# SensorBreakout.net
KiCad netlist of a schematic drawn in Altium Designer
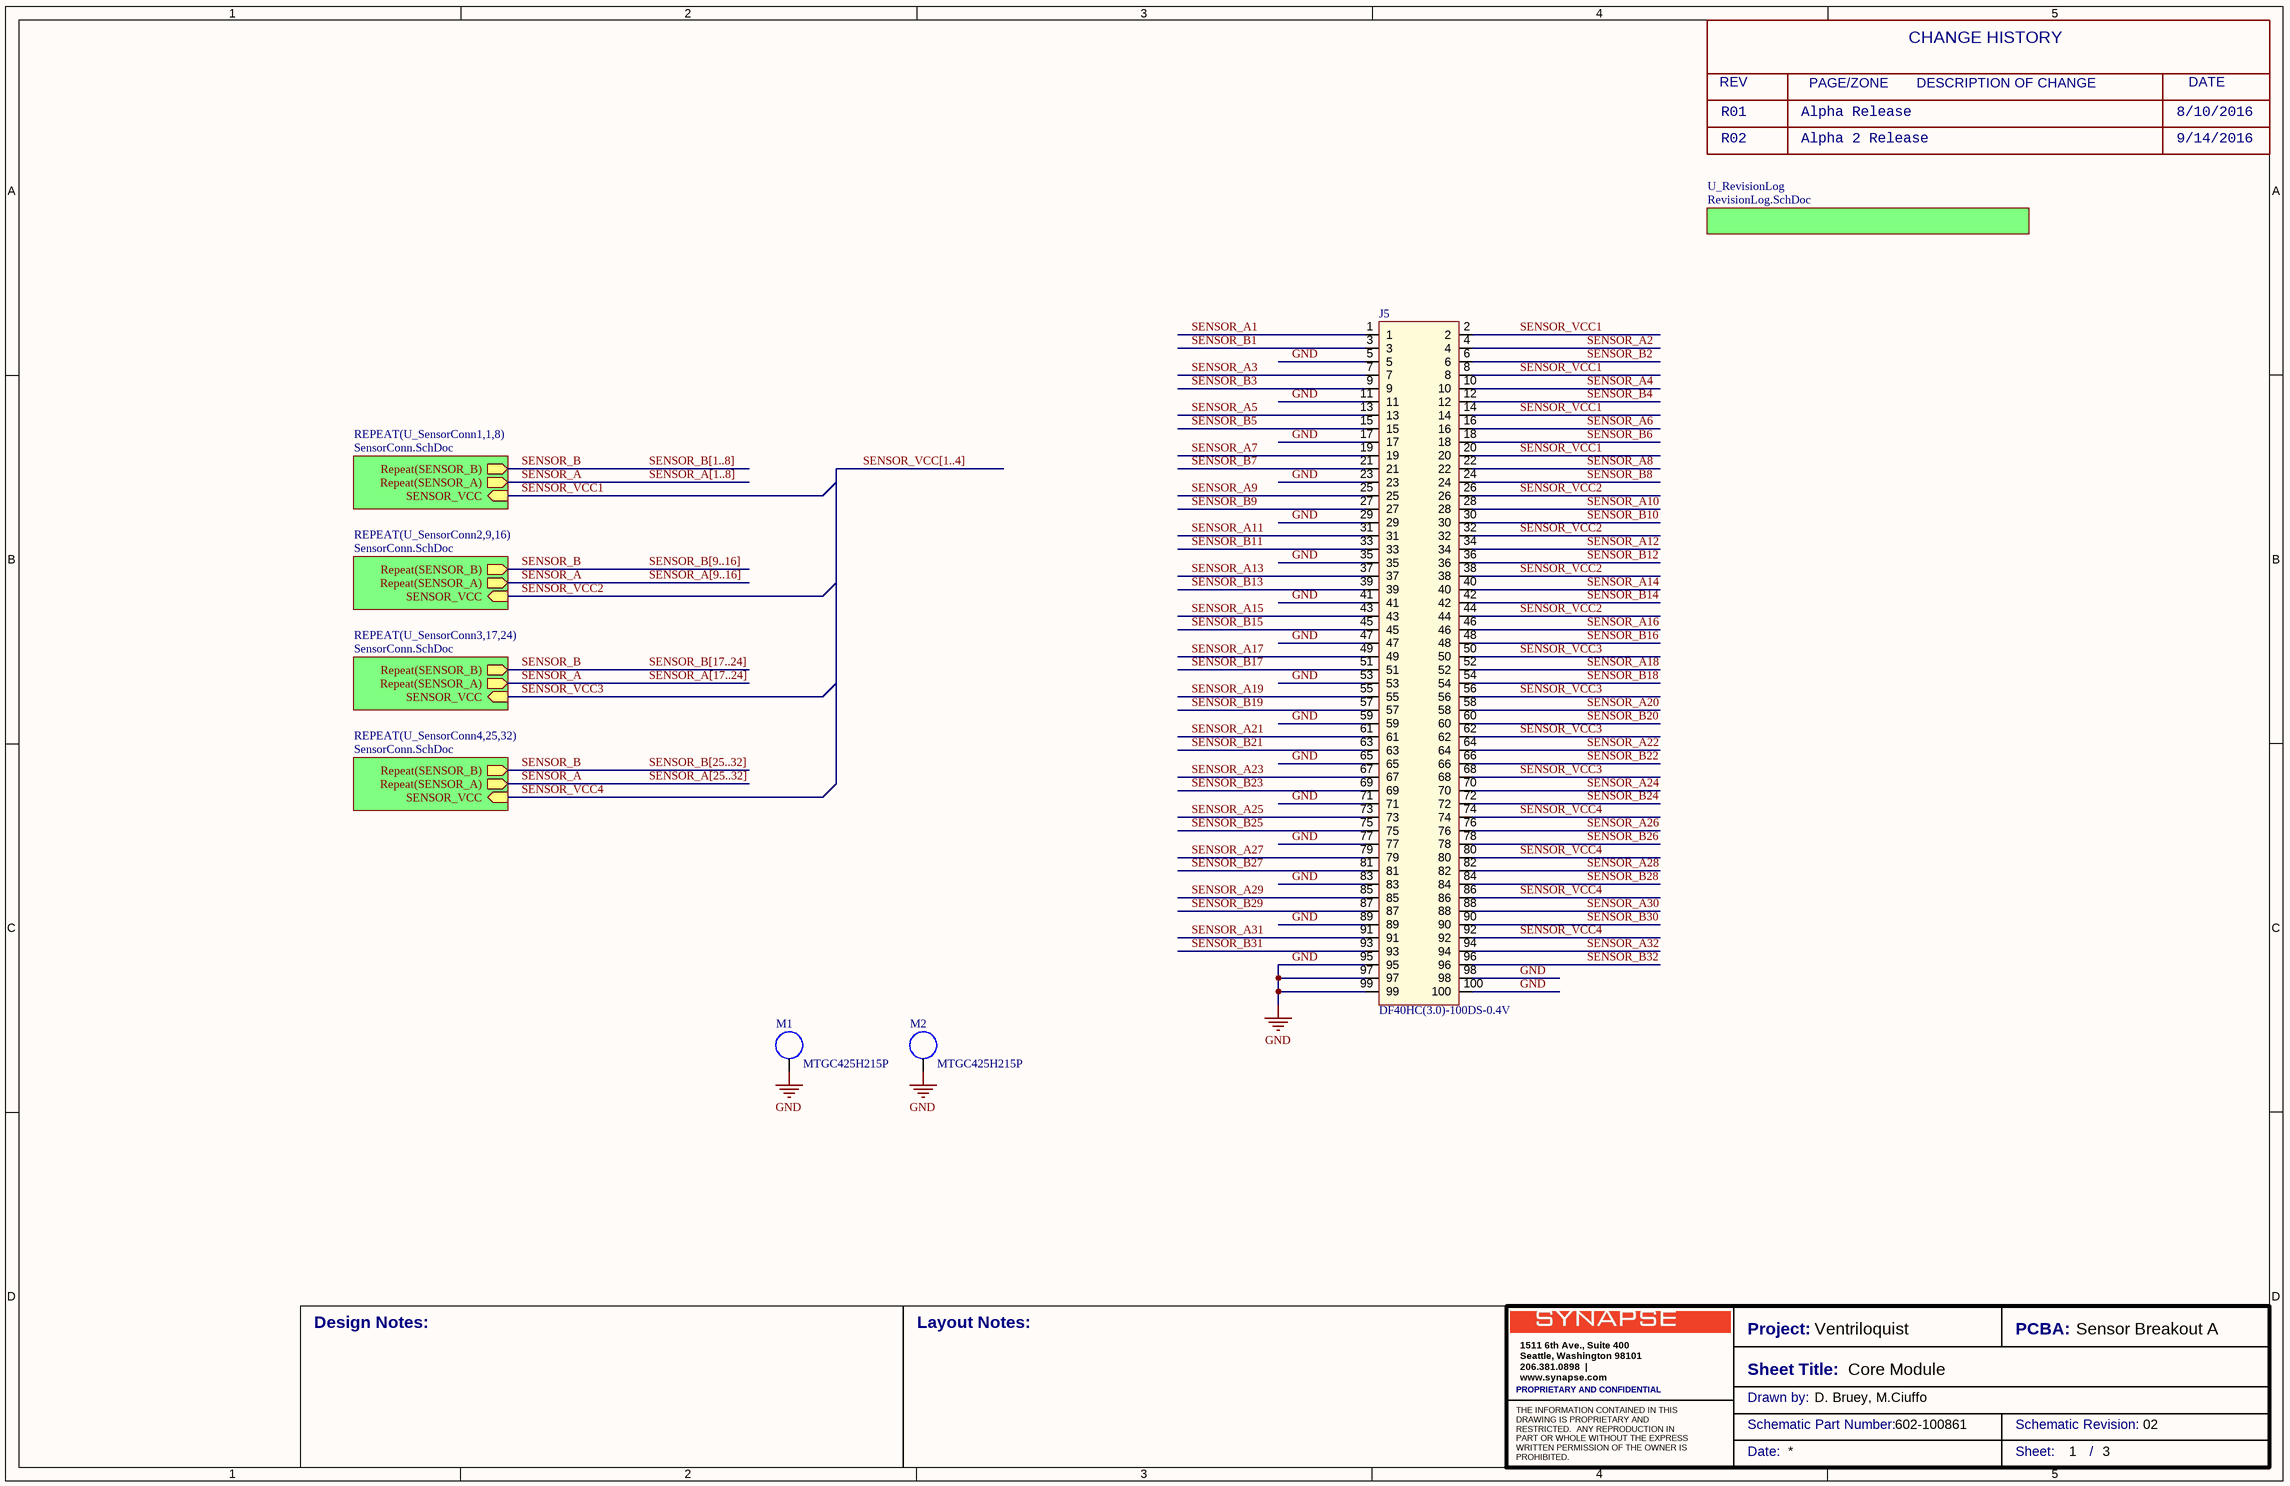
[diagram p0: SensorBreakout.SchDoc]

(export (version "E")
  (design (tool "Eeschema 10.0.6"))
  (components
    (comp (ref "J5")
      (value "DF40HC(3.0)-100DS-0.4V")
      (footprint "con100_hirose-df40c-100ds_129h")
      (description "CONN RCPT 100POS 0.4MM SMD GOLD 3.0MM")
      (fields (field (name "MFG") "Hirose") (field (name "VOLTAGE") "30V"))
      (libsource (lib "SynapseLibrary") (part "DF40C-100DS-0.4(51)"))
    )
    (comp (ref "M1")
      (value "MTGC425H215P")
      (footprint "MTGC425H215P")
      (description "MTG, 4.25mm PAD, 2.15mm Plated Hole")
      (libsource (lib "SynapseLibrary") (part "MTG"))
    )
    (comp (ref "M2")
      (value "MTGC425H215P")
      (footprint "MTGC425H215P")
      (description "MTG, 4.25mm PAD, 2.15mm Plated Hole")
      (libsource (lib "SynapseLibrary") (part "MTG"))
    )
  )
  (nets
    (net (code "2") (name "/SENSOR_A1") (class "Default")
      (node (ref "J5") (pin "1") (pinfunction "1_1") (pintype "passive"))
    )
    (net (code "3") (name "/SENSOR_A2") (class "Default")
      (node (ref "J5") (pin "4") (pinfunction "4_4") (pintype "passive"))
    )
    (net (code "4") (name "/SENSOR_A3") (class "Default")
      (node (ref "J5") (pin "7") (pinfunction "7_7") (pintype "passive"))
    )
    (net (code "5") (name "/SENSOR_A4") (class "Default")
      (node (ref "J5") (pin "10") (pinfunction "10_10") (pintype "passive"))
    )
    (net (code "6") (name "/SENSOR_A5") (class "Default")
      (node (ref "J5") (pin "13") (pinfunction "13_13") (pintype "passive"))
    )
    (net (code "7") (name "/SENSOR_A6") (class "Default")
      (node (ref "J5") (pin "16") (pinfunction "16_16") (pintype "passive"))
    )
    (net (code "8") (name "/SENSOR_A7") (class "Default")
      (node (ref "J5") (pin "19") (pinfunction "19_19") (pintype "passive"))
    )
    (net (code "9") (name "/SENSOR_A8") (class "Default")
      (node (ref "J5") (pin "22") (pinfunction "22_22") (pintype "passive"))
    )
    (net (code "10") (name "/SENSOR_A9") (class "Default")
      (node (ref "J5") (pin "25") (pinfunction "25_25") (pintype "passive"))
    )
    (net (code "11") (name "/SENSOR_A10") (class "Default")
      (node (ref "J5") (pin "28") (pinfunction "28_28") (pintype "passive"))
    )
    (net (code "12") (name "/SENSOR_A11") (class "Default")
      (node (ref "J5") (pin "31") (pinfunction "31_31") (pintype "passive"))
    )
    (net (code "13") (name "/SENSOR_A12") (class "Default")
      (node (ref "J5") (pin "34") (pinfunction "34_34") (pintype "passive"))
    )
    (net (code "14") (name "/SENSOR_A13") (class "Default")
      (node (ref "J5") (pin "37") (pinfunction "37_37") (pintype "passive"))
    )
    (net (code "15") (name "/SENSOR_A14") (class "Default")
      (node (ref "J5") (pin "40") (pinfunction "40_40") (pintype "passive"))
    )
    (net (code "16") (name "/SENSOR_A15") (class "Default")
      (node (ref "J5") (pin "43") (pinfunction "43_43") (pintype "passive"))
    )
    (net (code "17") (name "/SENSOR_A16") (class "Default")
      (node (ref "J5") (pin "46") (pinfunction "46_46") (pintype "passive"))
    )
    (net (code "18") (name "/SENSOR_A17") (class "Default")
      (node (ref "J5") (pin "49") (pinfunction "49_49") (pintype "passive"))
    )
    (net (code "19") (name "/SENSOR_A18") (class "Default")
      (node (ref "J5") (pin "52") (pinfunction "52_52") (pintype "passive"))
    )
    (net (code "20") (name "/SENSOR_A19") (class "Default")
      (node (ref "J5") (pin "55") (pinfunction "55_55") (pintype "passive"))
    )
    (net (code "21") (name "/SENSOR_A20") (class "Default")
      (node (ref "J5") (pin "58") (pinfunction "58_58") (pintype "passive"))
    )
    (net (code "22") (name "/SENSOR_A21") (class "Default")
      (node (ref "J5") (pin "61") (pinfunction "61_61") (pintype "passive"))
    )
    (net (code "23") (name "/SENSOR_A22") (class "Default")
      (node (ref "J5") (pin "64") (pinfunction "64_64") (pintype "passive"))
    )
    (net (code "24") (name "/SENSOR_A23") (class "Default")
      (node (ref "J5") (pin "67") (pinfunction "67_67") (pintype "passive"))
    )
    (net (code "25") (name "/SENSOR_A24") (class "Default")
      (node (ref "J5") (pin "70") (pinfunction "70_70") (pintype "passive"))
    )
    (net (code "26") (name "/SENSOR_A25") (class "Default")
      (node (ref "J5") (pin "73") (pinfunction "73_73") (pintype "passive"))
    )
    (net (code "27") (name "/SENSOR_A26") (class "Default")
      (node (ref "J5") (pin "76") (pinfunction "76_76") (pintype "passive"))
    )
    (net (code "28") (name "/SENSOR_A27") (class "Default")
      (node (ref "J5") (pin "79") (pinfunction "79_79") (pintype "passive"))
    )
    (net (code "29") (name "/SENSOR_A28") (class "Default")
      (node (ref "J5") (pin "82") (pinfunction "82_82") (pintype "passive"))
    )
    (net (code "30") (name "/SENSOR_A29") (class "Default")
      (node (ref "J5") (pin "85") (pinfunction "85_85") (pintype "passive"))
    )
    (net (code "31") (name "/SENSOR_A30") (class "Default")
      (node (ref "J5") (pin "88") (pinfunction "88_88") (pintype "passive"))
    )
    (net (code "32") (name "/SENSOR_A31") (class "Default")
      (node (ref "J5") (pin "91") (pinfunction "91_91") (pintype "passive"))
    )
    (net (code "33") (name "/SENSOR_A32") (class "Default")
      (node (ref "J5") (pin "94") (pinfunction "94_94") (pintype "passive"))
    )
    (net (code "39") (name "/SENSOR_B1") (class "Default")
      (node (ref "J5") (pin "3") (pinfunction "3_3") (pintype "passive"))
    )
    (net (code "40") (name "/SENSOR_B2") (class "Default")
      (node (ref "J5") (pin "6") (pinfunction "6_6") (pintype "passive"))
    )
    (net (code "41") (name "/SENSOR_B3") (class "Default")
      (node (ref "J5") (pin "9") (pinfunction "9_9") (pintype "passive"))
    )
    (net (code "42") (name "/SENSOR_B4") (class "Default")
      (node (ref "J5") (pin "12") (pinfunction "12_12") (pintype "passive"))
    )
    (net (code "43") (name "/SENSOR_B5") (class "Default")
      (node (ref "J5") (pin "15") (pinfunction "15_15") (pintype "passive"))
    )
    (net (code "44") (name "/SENSOR_B6") (class "Default")
      (node (ref "J5") (pin "18") (pinfunction "18_18") (pintype "passive"))
    )
    (net (code "45") (name "/SENSOR_B7") (class "Default")
      (node (ref "J5") (pin "21") (pinfunction "21_21") (pintype "passive"))
    )
    (net (code "46") (name "/SENSOR_B8") (class "Default")
      (node (ref "J5") (pin "24") (pinfunction "24_24") (pintype "passive"))
    )
    (net (code "47") (name "/SENSOR_B9") (class "Default")
      (node (ref "J5") (pin "27") (pinfunction "27_27") (pintype "passive"))
    )
    (net (code "48") (name "/SENSOR_B10") (class "Default")
      (node (ref "J5") (pin "30") (pinfunction "30_30") (pintype "passive"))
    )
    (net (code "49") (name "/SENSOR_B11") (class "Default")
      (node (ref "J5") (pin "33") (pinfunction "33_33") (pintype "passive"))
    )
    (net (code "50") (name "/SENSOR_B12") (class "Default")
      (node (ref "J5") (pin "36") (pinfunction "36_36") (pintype "passive"))
    )
    (net (code "51") (name "/SENSOR_B13") (class "Default")
      (node (ref "J5") (pin "39") (pinfunction "39_39") (pintype "passive"))
    )
    (net (code "52") (name "/SENSOR_B14") (class "Default")
      (node (ref "J5") (pin "42") (pinfunction "42_42") (pintype "passive"))
    )
    (net (code "53") (name "/SENSOR_B15") (class "Default")
      (node (ref "J5") (pin "45") (pinfunction "45_45") (pintype "passive"))
    )
    (net (code "54") (name "/SENSOR_B16") (class "Default")
      (node (ref "J5") (pin "48") (pinfunction "48_48") (pintype "passive"))
    )
    (net (code "55") (name "/SENSOR_B17") (class "Default")
      (node (ref "J5") (pin "51") (pinfunction "51_51") (pintype "passive"))
    )
    (net (code "56") (name "/SENSOR_B18") (class "Default")
      (node (ref "J5") (pin "54") (pinfunction "54_54") (pintype "passive"))
    )
    (net (code "57") (name "/SENSOR_B19") (class "Default")
      (node (ref "J5") (pin "57") (pinfunction "57_57") (pintype "passive"))
    )
    (net (code "58") (name "/SENSOR_B20") (class "Default")
      (node (ref "J5") (pin "60") (pinfunction "60_60") (pintype "passive"))
    )
    (net (code "59") (name "/SENSOR_B21") (class "Default")
      (node (ref "J5") (pin "63") (pinfunction "63_63") (pintype "passive"))
    )
    (net (code "60") (name "/SENSOR_B22") (class "Default")
      (node (ref "J5") (pin "66") (pinfunction "66_66") (pintype "passive"))
    )
    (net (code "61") (name "/SENSOR_B23") (class "Default")
      (node (ref "J5") (pin "69") (pinfunction "69_69") (pintype "passive"))
    )
    (net (code "62") (name "/SENSOR_B24") (class "Default")
      (node (ref "J5") (pin "72") (pinfunction "72_72") (pintype "passive"))
    )
    (net (code "63") (name "/SENSOR_B25") (class "Default")
      (node (ref "J5") (pin "75") (pinfunction "75_75") (pintype "passive"))
    )
    (net (code "64") (name "/SENSOR_B26") (class "Default")
      (node (ref "J5") (pin "78") (pinfunction "78_78") (pintype "passive"))
    )
    (net (code "65") (name "/SENSOR_B27") (class "Default")
      (node (ref "J5") (pin "81") (pinfunction "81_81") (pintype "passive"))
    )
    (net (code "66") (name "/SENSOR_B28") (class "Default")
      (node (ref "J5") (pin "84") (pinfunction "84_84") (pintype "passive"))
    )
    (net (code "67") (name "/SENSOR_B29") (class "Default")
      (node (ref "J5") (pin "87") (pinfunction "87_87") (pintype "passive"))
    )
    (net (code "68") (name "/SENSOR_B30") (class "Default")
      (node (ref "J5") (pin "90") (pinfunction "90_90") (pintype "passive"))
    )
    (net (code "69") (name "/SENSOR_B31") (class "Default")
      (node (ref "J5") (pin "93") (pinfunction "93_93") (pintype "passive"))
    )
    (net (code "70") (name "/SENSOR_B32") (class "Default")
      (node (ref "J5") (pin "96") (pinfunction "96_96") (pintype "passive"))
    )
    (net (code "75") (name "/SENSOR_VCC1") (class "Default")
      (node (ref "J5") (pin "14") (pinfunction "14_14") (pintype "passive"))
      (node (ref "J5") (pin "2") (pinfunction "2_2") (pintype "passive"))
      (node (ref "J5") (pin "20") (pinfunction "20_20") (pintype "passive"))
      (node (ref "J5") (pin "8") (pinfunction "8_8") (pintype "passive"))
    )
    (net (code "76") (name "/SENSOR_VCC2") (class "Default")
      (node (ref "J5") (pin "26") (pinfunction "26_26") (pintype "passive"))
      (node (ref "J5") (pin "32") (pinfunction "32_32") (pintype "passive"))
      (node (ref "J5") (pin "38") (pinfunction "38_38") (pintype "passive"))
      (node (ref "J5") (pin "44") (pinfunction "44_44") (pintype "passive"))
    )
    (net (code "77") (name "/SENSOR_VCC3") (class "Default")
      (node (ref "J5") (pin "50") (pinfunction "50_50") (pintype "passive"))
      (node (ref "J5") (pin "56") (pinfunction "56_56") (pintype "passive"))
      (node (ref "J5") (pin "62") (pinfunction "62_62") (pintype "passive"))
      (node (ref "J5") (pin "68") (pinfunction "68_68") (pintype "passive"))
    )
    (net (code "78") (name "/SENSOR_VCC4") (class "Default")
      (node (ref "J5") (pin "74") (pinfunction "74_74") (pintype "passive"))
      (node (ref "J5") (pin "80") (pinfunction "80_80") (pintype "passive"))
      (node (ref "J5") (pin "86") (pinfunction "86_86") (pintype "passive"))
      (node (ref "J5") (pin "92") (pinfunction "92_92") (pintype "passive"))
    )
    (net (code "80") (name "GND") (class "Default")
      (node (ref "J5") (pin "100") (pinfunction "100_100") (pintype "passive"))
      (node (ref "J5") (pin "11") (pinfunction "11_11") (pintype "passive"))
      (node (ref "J5") (pin "17") (pinfunction "17_17") (pintype "passive"))
      (node (ref "J5") (pin "23") (pinfunction "23_23") (pintype "passive"))
      (node (ref "J5") (pin "29") (pinfunction "29_29") (pintype "passive"))
      (node (ref "J5") (pin "35") (pinfunction "35_35") (pintype "passive"))
      (node (ref "J5") (pin "41") (pinfunction "41_41") (pintype "passive"))
      (node (ref "J5") (pin "47") (pinfunction "47_47") (pintype "passive"))
      (node (ref "J5") (pin "5") (pinfunction "5_5") (pintype "passive"))
      (node (ref "J5") (pin "53") (pinfunction "53_53") (pintype "passive"))
      (node (ref "J5") (pin "59") (pinfunction "59_59") (pintype "passive"))
      (node (ref "J5") (pin "65") (pinfunction "65_65") (pintype "passive"))
      (node (ref "J5") (pin "71") (pinfunction "71_71") (pintype "passive"))
      (node (ref "J5") (pin "77") (pinfunction "77_77") (pintype "passive"))
      (node (ref "J5") (pin "83") (pinfunction "83_83") (pintype "passive"))
      (node (ref "J5") (pin "89") (pinfunction "89_89") (pintype "passive"))
      (node (ref "J5") (pin "95") (pinfunction "95_95") (pintype "passive"))
      (node (ref "J5") (pin "97") (pinfunction "97_97") (pintype "passive"))
      (node (ref "J5") (pin "98") (pinfunction "98_98") (pintype "passive"))
      (node (ref "J5") (pin "99") (pinfunction "99_99") (pintype "passive"))
      (node (ref "M1") (pin "1") (pinfunction "1_1") (pintype "passive"))
      (node (ref "M2") (pin "1") (pinfunction "1_1") (pintype "passive"))
    )
  )
)
